# Load_Switches.net
KiCad netlist of a schematic drawn in Altium Designer
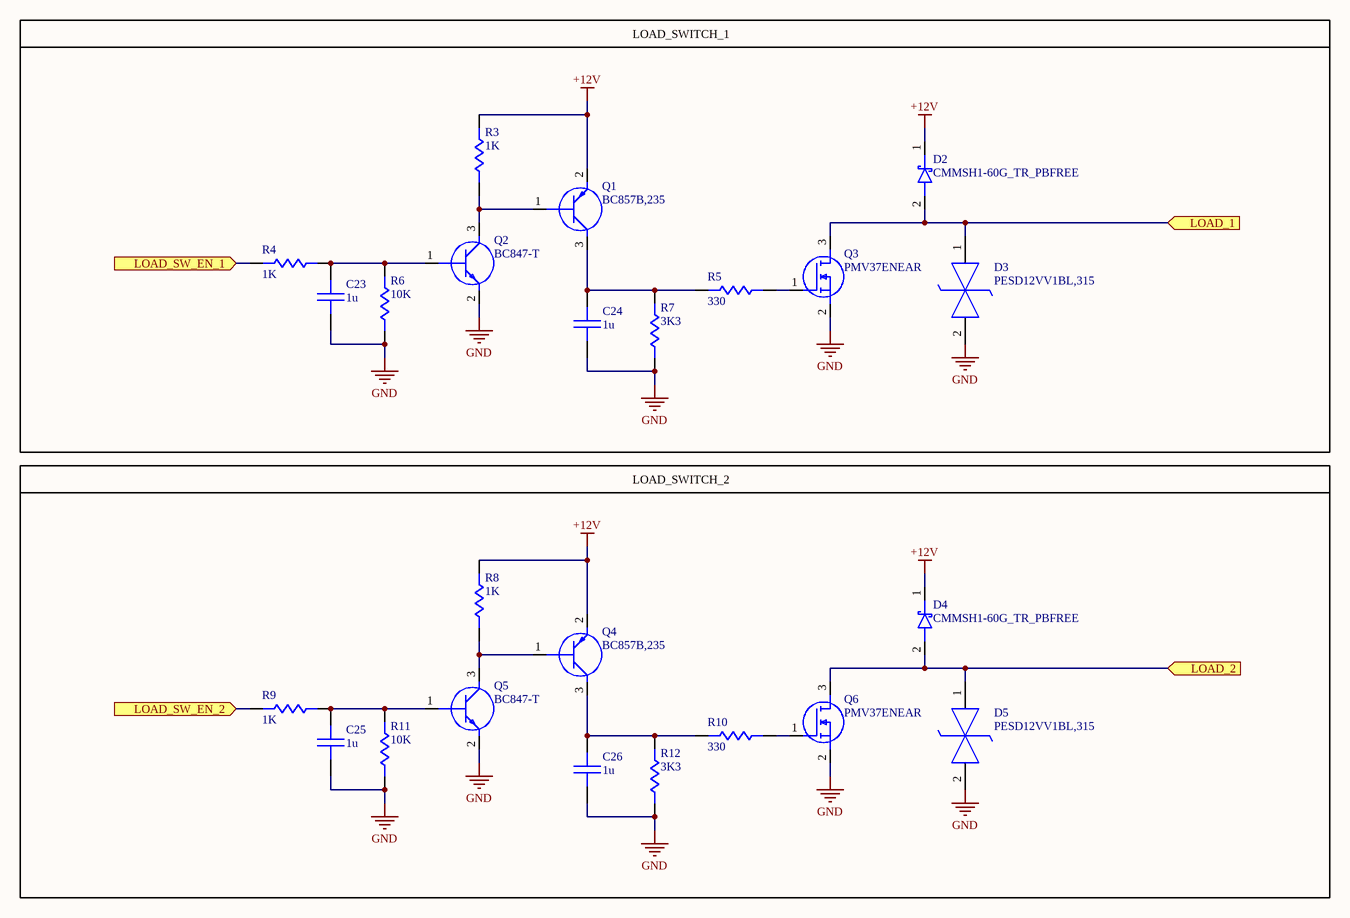
[diagram p0: Load_Switches.SchDoc]

(export (version "E")
  (design (tool "Eeschema 10.0.6"))
  (components
    (comp (ref "C23")
      (value "1u")
      (footprint "C_0603")
      (description "SMD Chip Capacitor")
      (libsource (lib "My_Integrated_Lib") (part "CAP"))
    )
    (comp (ref "C24")
      (value "1u")
      (footprint "C_0603")
      (description "SMD Chip Capacitor")
      (libsource (lib "My_Integrated_Lib") (part "CAP"))
    )
    (comp (ref "C25")
      (value "1u")
      (footprint "C_0603")
      (description "SMD Chip Capacitor")
      (libsource (lib "My_Integrated_Lib") (part "CAP"))
    )
    (comp (ref "C26")
      (value "1u")
      (footprint "C_0603")
      (description "SMD Chip Capacitor")
      (libsource (lib "My_Integrated_Lib") (part "CAP"))
    )
    (comp (ref "D2")
      (value "CMMSH1-60G_TR_PBFREE")
      (footprint "SOD-123-2")
      (description "Schottky Diodes & Rectifiers")
      (libsource (lib "My_Integrated_Lib") (part "DIODE_SCHOTTKY_CMMSH1-60G_TR_PBFREE"))
    )
    (comp (ref "D3")
      (value "PESD12VV1BL,315")
      (footprint "PESD5V0S1BL315")
      (description "Diode ESD (Bi-directional)")
      (fields (field (name "MOUSER PART NUMBER") "771-PESD12VV1BL,315"))
      (libsource (lib "My_Integrated_Lib") (part "PESD12VV1BL,315"))
    )
    (comp (ref "D4")
      (value "CMMSH1-60G_TR_PBFREE")
      (footprint "SOD-123-2")
      (description "Schottky Diodes & Rectifiers")
      (libsource (lib "My_Integrated_Lib") (part "DIODE_SCHOTTKY_CMMSH1-60G_TR_PBFREE"))
    )
    (comp (ref "D5")
      (value "PESD12VV1BL,315")
      (footprint "PESD5V0S1BL315")
      (description "Diode ESD (Bi-directional)")
      (fields (field (name "MOUSER PART NUMBER") "771-PESD12VV1BL,315"))
      (libsource (lib "My_Integrated_Lib") (part "PESD12VV1BL,315"))
    )
    (comp (ref "Q1")
      (value "BC857B,235")
      (footprint "SOT95P230X110-3N")
      (description "Transistor BJT PNP")
      (fields (field (name "MOUSER PART NUMBER") "771-BC857B235"))
      (libsource (lib "My_Integrated_Lib") (part "BC857B,235"))
    )
    (comp (ref "Q2")
      (value "BC847-T")
      (footprint "SOT95P240X115-3N")
      (description "Transistor BJT NPN")
      (fields (field (name "MOUSER PART NUMBER") "583-BC847"))
      (libsource (lib "My_Integrated_Lib") (part "BC847-T"))
    )
    (comp (ref "Q3")
      (value "PMV37ENEAR")
      (footprint "SOT95P230X110-3N")
      (description "MOSFET (N-Channel)")
      (fields (field (name "MOUSER PART NUMBER") "771-PMV37ENEAR"))
      (libsource (lib "My_Integrated_Lib") (part "PMV37ENEAR"))
    )
    (comp (ref "Q4")
      (value "BC857B,235")
      (footprint "SOT95P230X110-3N")
      (description "Transistor BJT PNP")
      (fields (field (name "MOUSER PART NUMBER") "771-BC857B235"))
      (libsource (lib "My_Integrated_Lib") (part "BC857B,235"))
    )
    (comp (ref "Q5")
      (value "BC847-T")
      (footprint "SOT95P240X115-3N")
      (description "Transistor BJT NPN")
      (fields (field (name "MOUSER PART NUMBER") "583-BC847"))
      (libsource (lib "My_Integrated_Lib") (part "BC847-T"))
    )
    (comp (ref "Q6")
      (value "PMV37ENEAR")
      (footprint "SOT95P230X110-3N")
      (description "MOSFET (N-Channel)")
      (fields (field (name "MOUSER PART NUMBER") "771-PMV37ENEAR"))
      (libsource (lib "My_Integrated_Lib") (part "PMV37ENEAR"))
    )
    (comp (ref "R3")
      (value "1K")
      (footprint "R_0603")
      (description "SMD Chip Resistor")
      (libsource (lib "My_Integrated_Lib") (part "RES"))
    )
    (comp (ref "R4")
      (value "1K")
      (footprint "R_0603")
      (description "SMD Chip Resistor")
      (libsource (lib "My_Integrated_Lib") (part "RES"))
    )
    (comp (ref "R5")
      (value "330")
      (footprint "R_0603")
      (description "SMD Chip Resistor")
      (libsource (lib "My_Integrated_Lib") (part "RES"))
    )
    (comp (ref "R6")
      (value "10K")
      (footprint "R_0603")
      (description "SMD Chip Resistor")
      (libsource (lib "My_Integrated_Lib") (part "RES"))
    )
    (comp (ref "R7")
      (value "3K3")
      (footprint "R_0603")
      (description "SMD Chip Resistor")
      (libsource (lib "My_Integrated_Lib") (part "RES"))
    )
    (comp (ref "R8")
      (value "1K")
      (footprint "R_0603")
      (description "SMD Chip Resistor")
      (libsource (lib "My_Integrated_Lib") (part "RES"))
    )
    (comp (ref "R9")
      (value "1K")
      (footprint "R_0603")
      (description "SMD Chip Resistor")
      (libsource (lib "My_Integrated_Lib") (part "RES"))
    )
    (comp (ref "R10")
      (value "330")
      (footprint "R_0603")
      (description "SMD Chip Resistor")
      (libsource (lib "My_Integrated_Lib") (part "RES"))
    )
    (comp (ref "R11")
      (value "10K")
      (footprint "R_0603")
      (description "SMD Chip Resistor")
      (libsource (lib "My_Integrated_Lib") (part "RES"))
    )
    (comp (ref "R12")
      (value "3K3")
      (footprint "R_0603")
      (description "SMD Chip Resistor")
      (libsource (lib "My_Integrated_Lib") (part "RES"))
    )
  )
  (nets
    (net (code "1") (name "+12V") (class "Default")
      (node (ref "D2") (pin "1") (pinfunction "K_1") (pintype "passive"))
      (node (ref "D4") (pin "1") (pinfunction "K_1") (pintype "passive"))
      (node (ref "Q1") (pin "2") (pinfunction "E_2") (pintype "passive"))
      (node (ref "Q4") (pin "2") (pinfunction "E_2") (pintype "passive"))
      (node (ref "R3") (pin "1") (pinfunction "1_1") (pintype "passive"))
      (node (ref "R8") (pin "1") (pinfunction "1_1") (pintype "passive"))
    )
    (net (code "2") (name "/LOAD_1") (class "Default")
      (node (ref "D2") (pin "2") (pinfunction "A_2") (pintype "passive"))
      (node (ref "D3") (pin "1") (pinfunction "K1_1") (pintype "passive"))
      (node (ref "Q3") (pin "3") (pinfunction "D_3") (pintype "passive"))
    )
    (net (code "3") (name "/LOAD_2") (class "Default")
      (node (ref "D4") (pin "2") (pinfunction "A_2") (pintype "passive"))
      (node (ref "D5") (pin "1") (pinfunction "K1_1") (pintype "passive"))
      (node (ref "Q6") (pin "3") (pinfunction "D_3") (pintype "passive"))
    )
    (net (code "4") (name "/LOAD_SW_EN_1") (class "Default")
      (node (ref "R4") (pin "1") (pinfunction "1_1") (pintype "passive"))
    )
    (net (code "5") (name "/LOAD_SW_EN_2") (class "Default")
      (node (ref "R9") (pin "1") (pinfunction "1_1") (pintype "passive"))
    )
    (net (code "6") (name "GND") (class "Default")
      (node (ref "C23") (pin "2") (pinfunction "2_2") (pintype "passive"))
      (node (ref "C24") (pin "2") (pinfunction "2_2") (pintype "passive"))
      (node (ref "C25") (pin "2") (pinfunction "2_2") (pintype "passive"))
      (node (ref "C26") (pin "2") (pinfunction "2_2") (pintype "passive"))
      (node (ref "D3") (pin "2") (pinfunction "K2_2") (pintype "passive"))
      (node (ref "D5") (pin "2") (pinfunction "K2_2") (pintype "passive"))
      (node (ref "Q2") (pin "2") (pinfunction "E_2") (pintype "passive"))
      (node (ref "Q3") (pin "2") (pinfunction "S_2") (pintype "passive"))
      (node (ref "Q5") (pin "2") (pinfunction "E_2") (pintype "passive"))
      (node (ref "Q6") (pin "2") (pinfunction "S_2") (pintype "passive"))
      (node (ref "R11") (pin "2") (pinfunction "2_2") (pintype "passive"))
      (node (ref "R12") (pin "2") (pinfunction "2_2") (pintype "passive"))
      (node (ref "R6") (pin "2") (pinfunction "2_2") (pintype "passive"))
      (node (ref "R7") (pin "2") (pinfunction "2_2") (pintype "passive"))
    )
    (net (code "7") (name "Net-(Q1-B)") (class "Default")
      (node (ref "Q1") (pin "1") (pinfunction "B_1") (pintype "passive"))
      (node (ref "Q2") (pin "3") (pinfunction "C_3") (pintype "passive"))
      (node (ref "R3") (pin "2") (pinfunction "2_2") (pintype "passive"))
    )
    (net (code "8") (name "Net-(Q1-C)") (class "Default")
      (node (ref "C24") (pin "1") (pinfunction "1_1") (pintype "passive"))
      (node (ref "Q1") (pin "3") (pinfunction "C_3") (pintype "passive"))
      (node (ref "R5") (pin "2") (pinfunction "2_2") (pintype "passive"))
      (node (ref "R7") (pin "1") (pinfunction "1_1") (pintype "passive"))
    )
    (net (code "9") (name "Net-(Q2-B)") (class "Default")
      (node (ref "C23") (pin "1") (pinfunction "1_1") (pintype "passive"))
      (node (ref "Q2") (pin "1") (pinfunction "B_1") (pintype "passive"))
      (node (ref "R4") (pin "2") (pinfunction "2_2") (pintype "passive"))
      (node (ref "R6") (pin "1") (pinfunction "1_1") (pintype "passive"))
    )
    (net (code "10") (name "Net-(Q3-G)") (class "Default")
      (node (ref "Q3") (pin "1") (pinfunction "G_1") (pintype "passive"))
      (node (ref "R5") (pin "1") (pinfunction "1_1") (pintype "passive"))
    )
    (net (code "11") (name "Net-(Q4-B)") (class "Default")
      (node (ref "Q4") (pin "1") (pinfunction "B_1") (pintype "passive"))
      (node (ref "Q5") (pin "3") (pinfunction "C_3") (pintype "passive"))
      (node (ref "R8") (pin "2") (pinfunction "2_2") (pintype "passive"))
    )
    (net (code "12") (name "Net-(Q4-C)") (class "Default")
      (node (ref "C26") (pin "1") (pinfunction "1_1") (pintype "passive"))
      (node (ref "Q4") (pin "3") (pinfunction "C_3") (pintype "passive"))
      (node (ref "R10") (pin "2") (pinfunction "2_2") (pintype "passive"))
      (node (ref "R12") (pin "1") (pinfunction "1_1") (pintype "passive"))
    )
    (net (code "13") (name "Net-(Q5-B)") (class "Default")
      (node (ref "C25") (pin "1") (pinfunction "1_1") (pintype "passive"))
      (node (ref "Q5") (pin "1") (pinfunction "B_1") (pintype "passive"))
      (node (ref "R11") (pin "1") (pinfunction "1_1") (pintype "passive"))
      (node (ref "R9") (pin "2") (pinfunction "2_2") (pintype "passive"))
    )
    (net (code "14") (name "Net-(Q6-G)") (class "Default")
      (node (ref "Q6") (pin "1") (pinfunction "G_1") (pintype "passive"))
      (node (ref "R10") (pin "1") (pinfunction "1_1") (pintype "passive"))
    )
  )
)
